# 07-TCXO_Crystal.net
KiCad netlist of a schematic drawn in Altium Designer
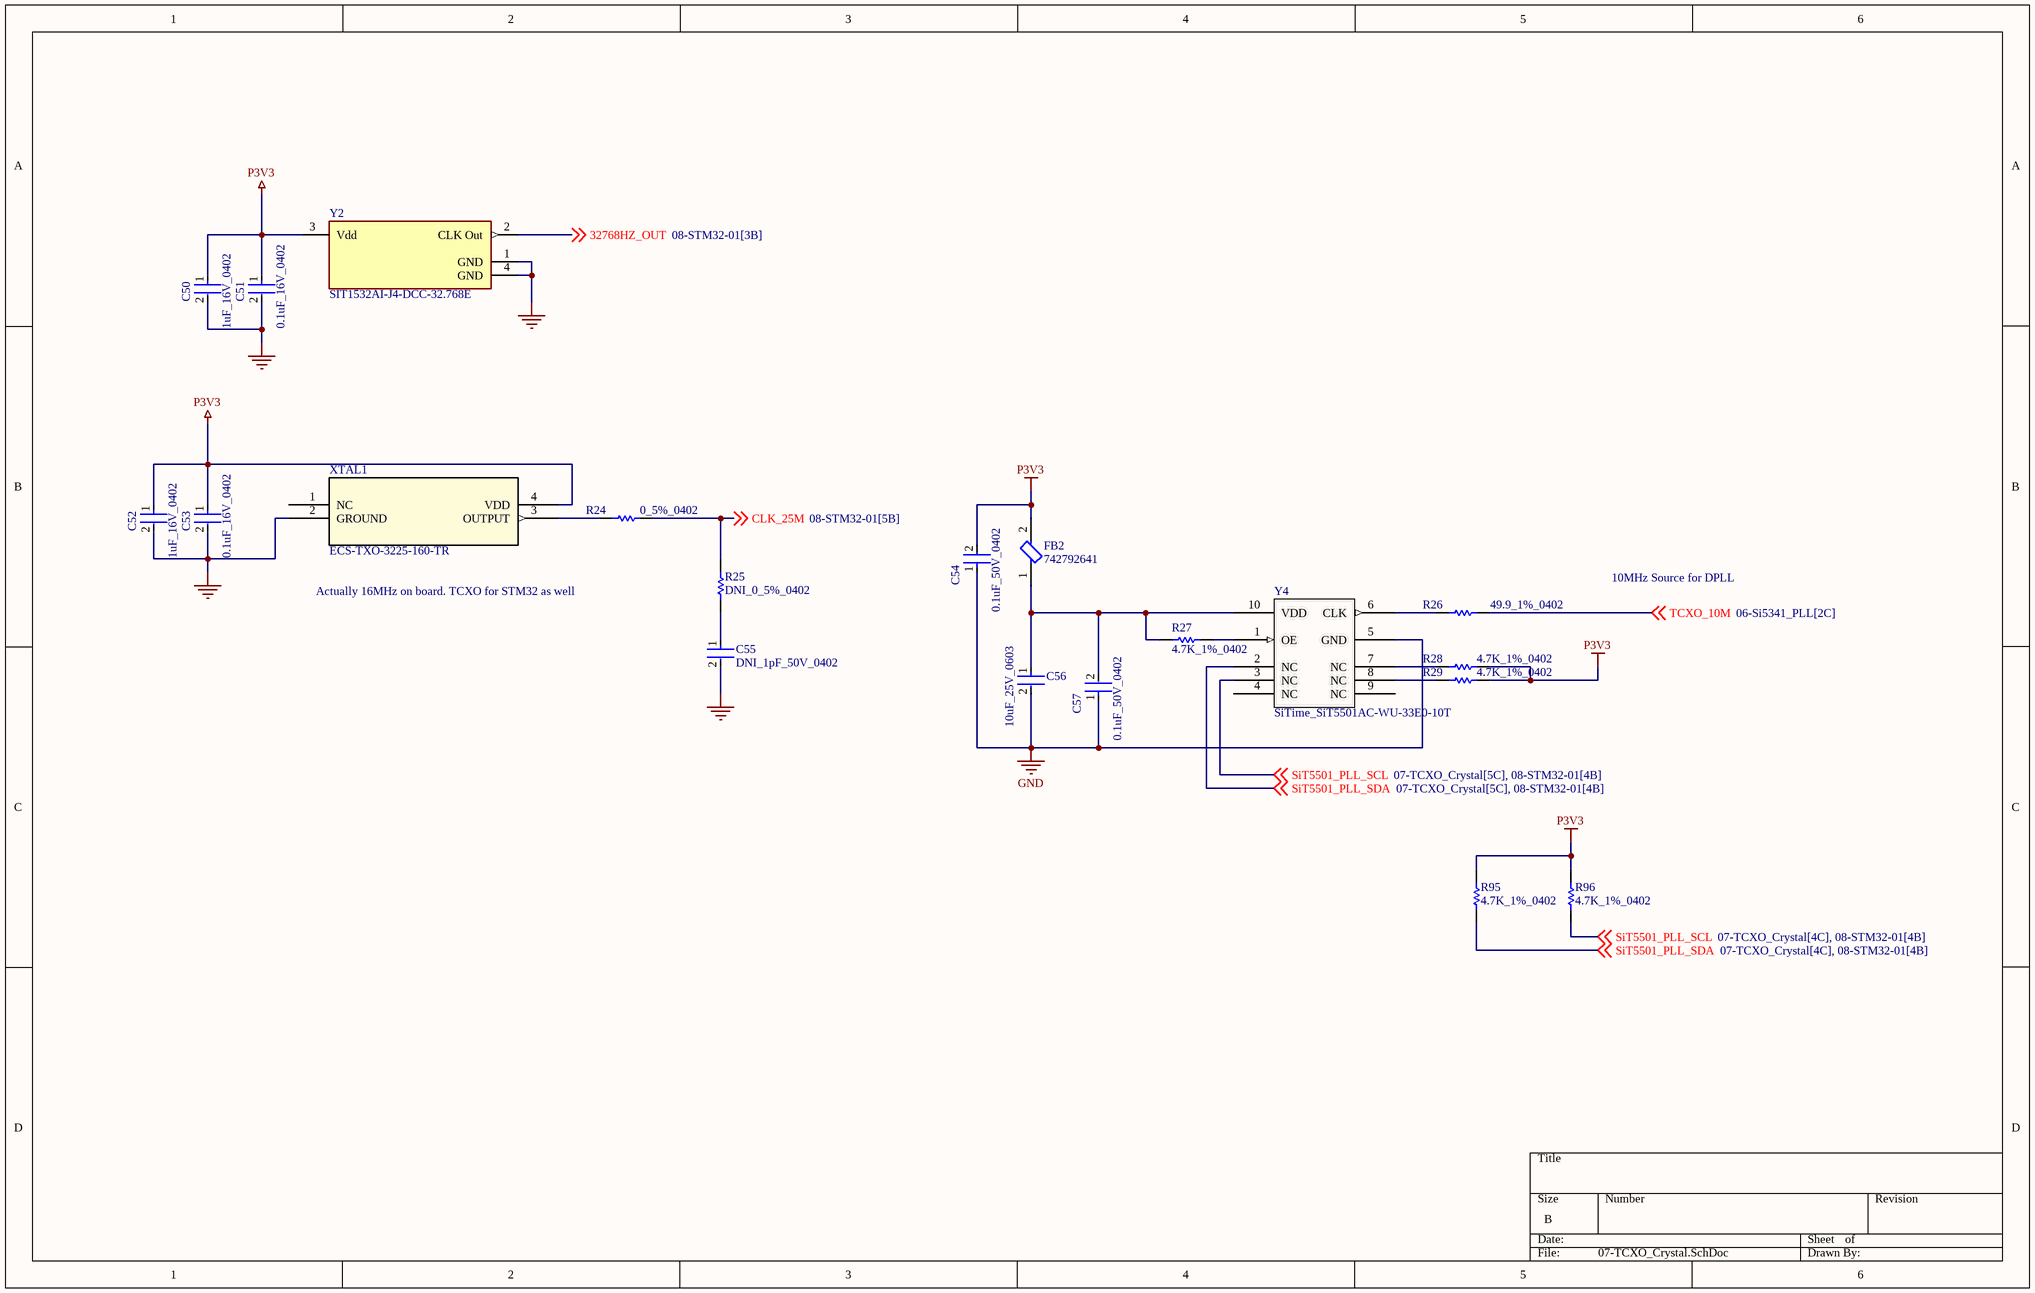
[diagram p0: 07-TCXO_Crystal.SchDoc]

(export (version "E")
  (design (tool "Eeschema 10.0.6"))
  (components
    (comp (ref "C50")
      (value "1uF_16V_0402")
      (footprint "FP-0402-L_1_0_0_05-W_0_5-IPC_A")
      (description "None")
      (fields (field (name "TOLERANCE") "10%"))
      (libsource (lib "Altium Content Vault") (part "b4654b650e69147ec39a6b967a45e02"))
    )
    (comp (ref "C51")
      (value "0.1uF_16V_0402")
      (footprint "FP-C0402-BB-MFG")
      (description "CAP CER 0.1UF 16V 5% X7R 0402")
      (fields
        (field (name "MANUFACTURER") "Kemet")
        (field (name "MANUFACTURER PART NUMBER") "C0402C104J4RACTU")
      )
      (libsource (lib "Altium Content Vault") (part "b4654b650e69147ec39a6b967a45e02"))
    )
    (comp (ref "C52")
      (value "1uF_16V_0402")
      (footprint "FP-0402-L_1_0_0_05-W_0_5-IPC_A")
      (description "None")
      (fields (field (name "TOLERANCE") "10%"))
      (libsource (lib "Altium Content Vault") (part "b4654b650e69147ec39a6b967a45e02"))
    )
    (comp (ref "C53")
      (value "0.1uF_16V_0402")
      (footprint "FP-C0402-BB-MFG")
      (description "CAP CER 0.1UF 16V 5% X7R 0402")
      (fields
        (field (name "MANUFACTURER") "Kemet")
        (field (name "MANUFACTURER PART NUMBER") "C0402C104J4RACTU")
      )
      (libsource (lib "Altium Content Vault") (part "b4654b650e69147ec39a6b967a45e02"))
    )
    (comp (ref "C54")
      (value "0.1uF_50V_0402")
      (footprint "FP-C1005-050-0_05-IPC_C")
      (description "Multilayer Ceramic Capacitors 100nF ±10% 50V X7R SMD 0402")
      (fields (field (name "VOLTAGE") "50V") (field (name "TOLERANCE") "10%"))
      (libsource (lib "Altium Content Vault") (part "b4654b650e69147ec39a6b967a45e02"))
    )
    (comp (ref "C55")
      (value "DNI_1pF_50V_0402")
      (footprint "FP-GJM155-0_05-IPC_B")
      (description "Multi-Layer Ceramic Capacitor 1pF C0G  ±0.1pF 0402 Paper T/R")
      (fields (field (name "VOLTAGE") "50V"))
      (libsource (lib "Altium Content Vault") (part "02cd4be3c70576c341d710602a673aa"))
    )
    (comp (ref "C56")
      (value "10uF_25V_0603")
      (footprint "FP-CL10-IPC_C")
      (description "Cap Ceramic 10uF 25V X5R ±20% Pad SMD 0603 +85°C T/R")
      (fields (field (name "TOLERANCE") "20%"))
      (libsource (lib "Altium Content Vault") (part "b4654b650e69147ec39a6b967a45e02"))
    )
    (comp (ref "C57")
      (value "0.1uF_50V_0402")
      (footprint "FP-C1005-050-0_05-IPC_C")
      (description "Multilayer Ceramic Capacitors 100nF ±10% 50V X7R SMD 0402")
      (fields (field (name "VOLTAGE") "50V") (field (name "TOLERANCE") "10%"))
      (libsource (lib "Altium Content Vault") (part "b4654b650e69147ec39a6b967a45e02"))
    )
    (comp (ref "FB2")
      (value "742792641")
      (footprint "FP-742792641-MFG")
      (description "FERRITE BEAD 300 OHM 0603 1LN")
      (fields (field (name "TOLERANCE") "25%"))
      (libsource (lib "Altium Content Vault") (part "5f30dd21d616792df468990f7003faa"))
    )
    (comp (ref "R24")
      (value "0_5%_0402")
      (footprint "RESC1005X40X25NL05T10")
      (fields (field (name "MANUFACTURER") "Panasonic") (field (name "PART NUMBER") "ERJ-U020R00X"))
      (libsource (lib "Altium Content Vault") (part "RES"))
    )
    (comp (ref "R25")
      (value "DNI_0_5%_0402")
      (footprint "RESC1005X40X25NL05T10")
      (fields (field (name "MANUFACTURER") "Panasonic") (field (name "PART NUMBER") "ERJ-U020R00X"))
      (libsource (lib "Altium Content Vault") (part "RES"))
    )
    (comp (ref "R26")
      (value "49.9_1%_0402")
      (footprint "RESC1005X40X25NL10T10")
      (fields (field (name "PART NUMBER") "RK73H1ETTP49R9F") (field (name "MANUFACTURER") "KOA Speer"))
      (libsource (lib "Altium Content Vault") (part "RES"))
    )
    (comp (ref "R27")
      (value "4.7K_1%_0402")
      (footprint "RESC1005X40X25NL10T10")
      (fields (field (name "MANUFACTURER") "Bourns") (field (name "PART NUMBER") "CR0402-FX-4701GLF"))
      (libsource (lib "Altium Content Vault") (part "RES"))
    )
    (comp (ref "R28")
      (value "4.7K_1%_0402")
      (footprint "RESC1005X40X25NL10T10")
      (fields (field (name "MANUFACTURER") "Bourns") (field (name "PART NUMBER") "CR0402-FX-4701GLF"))
      (libsource (lib "Altium Content Vault") (part "RES"))
    )
    (comp (ref "R29")
      (value "4.7K_1%_0402")
      (footprint "RESC1005X40X25NL10T10")
      (fields (field (name "MANUFACTURER") "Bourns") (field (name "PART NUMBER") "CR0402-FX-4701GLF"))
      (libsource (lib "Altium Content Vault") (part "RES"))
    )
    (comp (ref "R95")
      (value "4.7K_1%_0402")
      (footprint "RESC1005X40X25NL10T10")
      (fields (field (name "MANUFACTURER") "Bourns") (field (name "PART NUMBER") "CR0402-FX-4701GLF"))
      (libsource (lib "Altium Content Vault") (part "RES"))
    )
    (comp (ref "R96")
      (value "4.7K_1%_0402")
      (footprint "RESC1005X40X25NL10T10")
      (fields (field (name "MANUFACTURER") "Bourns") (field (name "PART NUMBER") "CR0402-FX-4701GLF"))
      (libsource (lib "Altium Content Vault") (part "RES"))
    )
    (comp (ref "XTAL1")
      (value "ECS-TXO-3225-160-TR")
      (footprint "ECS-TXO-3225_ECS")
      (description "No Description Available")
      (libsource (lib "ECS-TXO-3225-122P8-TR") (part "ECS-TXO-3225-122.8-TR"))
    )
    (comp (ref "Y2")
      (value "SIT1532AI-J4-DCC-32.768E")
      (footprint "FP-SIT1532-MFG")
      (description "MEMS OSC XO 32.7680KHZ LVCMOS")
      (libsource (lib "Altium Content Vault") (part "c4f9b1365e25d15033dfe34c89f26e6"))
    )
    (comp (ref "Y4")
      (value "SiTime_SiT5501AC-WU-33E0-10T")
      (footprint "SITIME_SPL-086-CQFN-010-C07050_REV_DRAFT")
      (description "OSC, MEMS, STRATUM 3E, 10.000MHZ, 10PPB STAB, LVCMOS, 3.3V, O/P EN, 7.0X5.0X2.2MM, CQFN-10")
      (fields
        (field (name "MANUFACTURER PART NUMBER") "SiT5501AI-WU033JH-10.000000")
        (field (name "MANUFACTURER") "SiTime")
      )
      (libsource (lib "OCXO_DaughterCard") (part "CMP-OSC-00029-2"))
    )
  )
  (nets
    (net (code "1") (name "32768HZ_OUT") (class "Default")
      (node (ref "Y2") (pin "2") (pinfunction "CLK_Out_2") (pintype "output"))
    )
    (net (code "2") (name "CLK_25M") (class "Default")
      (node (ref "R24") (pin "2") (pinfunction "2_2") (pintype "passive"))
      (node (ref "R25") (pin "2") (pinfunction "2_2") (pintype "passive"))
    )
    (net (code "3") (name "GND") (class "Default")
      (node (ref "C50") (pin "2") (pinfunction "2_2") (pintype "passive"))
      (node (ref "C51") (pin "2") (pinfunction "2_2") (pintype "passive"))
      (node (ref "C52") (pin "2") (pinfunction "2_2") (pintype "passive"))
      (node (ref "C53") (pin "2") (pinfunction "2_2") (pintype "passive"))
      (node (ref "C54") (pin "1") (pinfunction "1_1") (pintype "passive"))
      (node (ref "C55") (pin "2") (pinfunction "2_2") (pintype "passive"))
      (node (ref "C56") (pin "2") (pinfunction "2_2") (pintype "passive"))
      (node (ref "C57") (pin "1") (pinfunction "1_1") (pintype "passive"))
      (node (ref "XTAL1") (pin "2") (pinfunction "GROUND_2") (pintype "power_in"))
      (node (ref "Y2") (pin "1") (pinfunction "GND_1") (pintype "power_in"))
      (node (ref "Y2") (pin "4") (pinfunction "GND_4") (pintype "power_in"))
      (node (ref "Y4") (pin "5") (pinfunction "GND_5") (pintype "power_in"))
    )
    (net (code "4") (name "Net-(C55-Pad1)") (class "Default")
      (node (ref "C55") (pin "1") (pinfunction "1_1") (pintype "passive"))
      (node (ref "R25") (pin "1") (pinfunction "1_1") (pintype "passive"))
    )
    (net (code "5") (name "Net-(R28-Pad1)") (class "Default")
      (node (ref "R28") (pin "1") (pinfunction "1_1") (pintype "passive"))
      (node (ref "Y4") (pin "7") (pinfunction "NC_7") (pintype "passive"))
    )
    (net (code "6") (name "Net-(R29-Pad1)") (class "Default")
      (node (ref "R29") (pin "1") (pinfunction "1_1") (pintype "passive"))
      (node (ref "Y4") (pin "8") (pinfunction "NC_8") (pintype "passive"))
    )
    (net (code "7") (name "Net-(XTAL1-OUTPUT)") (class "Default")
      (node (ref "R24") (pin "1") (pinfunction "1_1") (pintype "passive"))
      (node (ref "XTAL1") (pin "3") (pinfunction "OUTPUT_3") (pintype "output"))
    )
    (net (code "8") (name "Net-(Y4-CLK)") (class "Default")
      (node (ref "R26") (pin "2") (pinfunction "2_2") (pintype "passive"))
      (node (ref "Y4") (pin "6") (pinfunction "CLK_6") (pintype "output"))
    )
    (net (code "9") (name "Net-(Y4-OE)") (class "Default")
      (node (ref "R27") (pin "2") (pinfunction "2_2") (pintype "passive"))
      (node (ref "Y4") (pin "1") (pinfunction "OE_1") (pintype "input"))
    )
    (net (code "10") (name "Net-(Y4-VDD)") (class "Default")
      (node (ref "C56") (pin "1") (pinfunction "1_1") (pintype "passive"))
      (node (ref "C57") (pin "2") (pinfunction "2_2") (pintype "passive"))
      (node (ref "FB2") (pin "1") (pinfunction "1_1") (pintype "passive"))
      (node (ref "R27") (pin "1") (pinfunction "1_1") (pintype "passive"))
      (node (ref "Y4") (pin "10") (pinfunction "VDD_10") (pintype "power_in"))
    )
    (net (code "11") (name "P3V3") (class "Default")
      (node (ref "C50") (pin "1") (pinfunction "1_1") (pintype "passive"))
      (node (ref "C51") (pin "1") (pinfunction "1_1") (pintype "passive"))
      (node (ref "C52") (pin "1") (pinfunction "1_1") (pintype "passive"))
      (node (ref "C53") (pin "1") (pinfunction "1_1") (pintype "passive"))
      (node (ref "C54") (pin "2") (pinfunction "2_2") (pintype "passive"))
      (node (ref "FB2") (pin "2") (pinfunction "2_2") (pintype "passive"))
      (node (ref "R28") (pin "2") (pinfunction "2_2") (pintype "passive"))
      (node (ref "R29") (pin "2") (pinfunction "2_2") (pintype "passive"))
      (node (ref "R95") (pin "2") (pinfunction "2_2") (pintype "passive"))
      (node (ref "R96") (pin "2") (pinfunction "2_2") (pintype "passive"))
      (node (ref "XTAL1") (pin "4") (pinfunction "VDD_4") (pintype "power_in"))
      (node (ref "Y2") (pin "3") (pinfunction "Vdd_3") (pintype "power_in"))
    )
    (net (code "12") (name "SiT5501_PLL_SCL") (class "Default")
      (node (ref "R96") (pin "1") (pinfunction "1_1") (pintype "passive"))
      (node (ref "Y4") (pin "3") (pinfunction "NC_3") (pintype "passive"))
    )
    (net (code "13") (name "SiT5501_PLL_SDA") (class "Default")
      (node (ref "R95") (pin "1") (pinfunction "1_1") (pintype "passive"))
      (node (ref "Y4") (pin "2") (pinfunction "NC_2") (pintype "passive"))
    )
    (net (code "14") (name "TCXO_10M") (class "Default")
      (node (ref "R26") (pin "1") (pinfunction "1_1") (pintype "passive"))
    )
    (net (code "15") (name "unconnected-(XTAL1-NC-Pad1)") (class "Default")
      (node (ref "XTAL1") (pin "1") (pinfunction "NC_1") (pintype "passive"))
    )
    (net (code "16") (name "unconnected-(Y4-NC-Pad4)") (class "Default")
      (node (ref "Y4") (pin "4") (pinfunction "NC_4") (pintype "passive"))
    )
    (net (code "17") (name "unconnected-(Y4-NC-Pad9)") (class "Default")
      (node (ref "Y4") (pin "9") (pinfunction "NC_9") (pintype "passive"))
    )
  )
)
